# SCH_MCP_41x_453x.net
KiCad netlist of a schematic drawn in Altium Designer
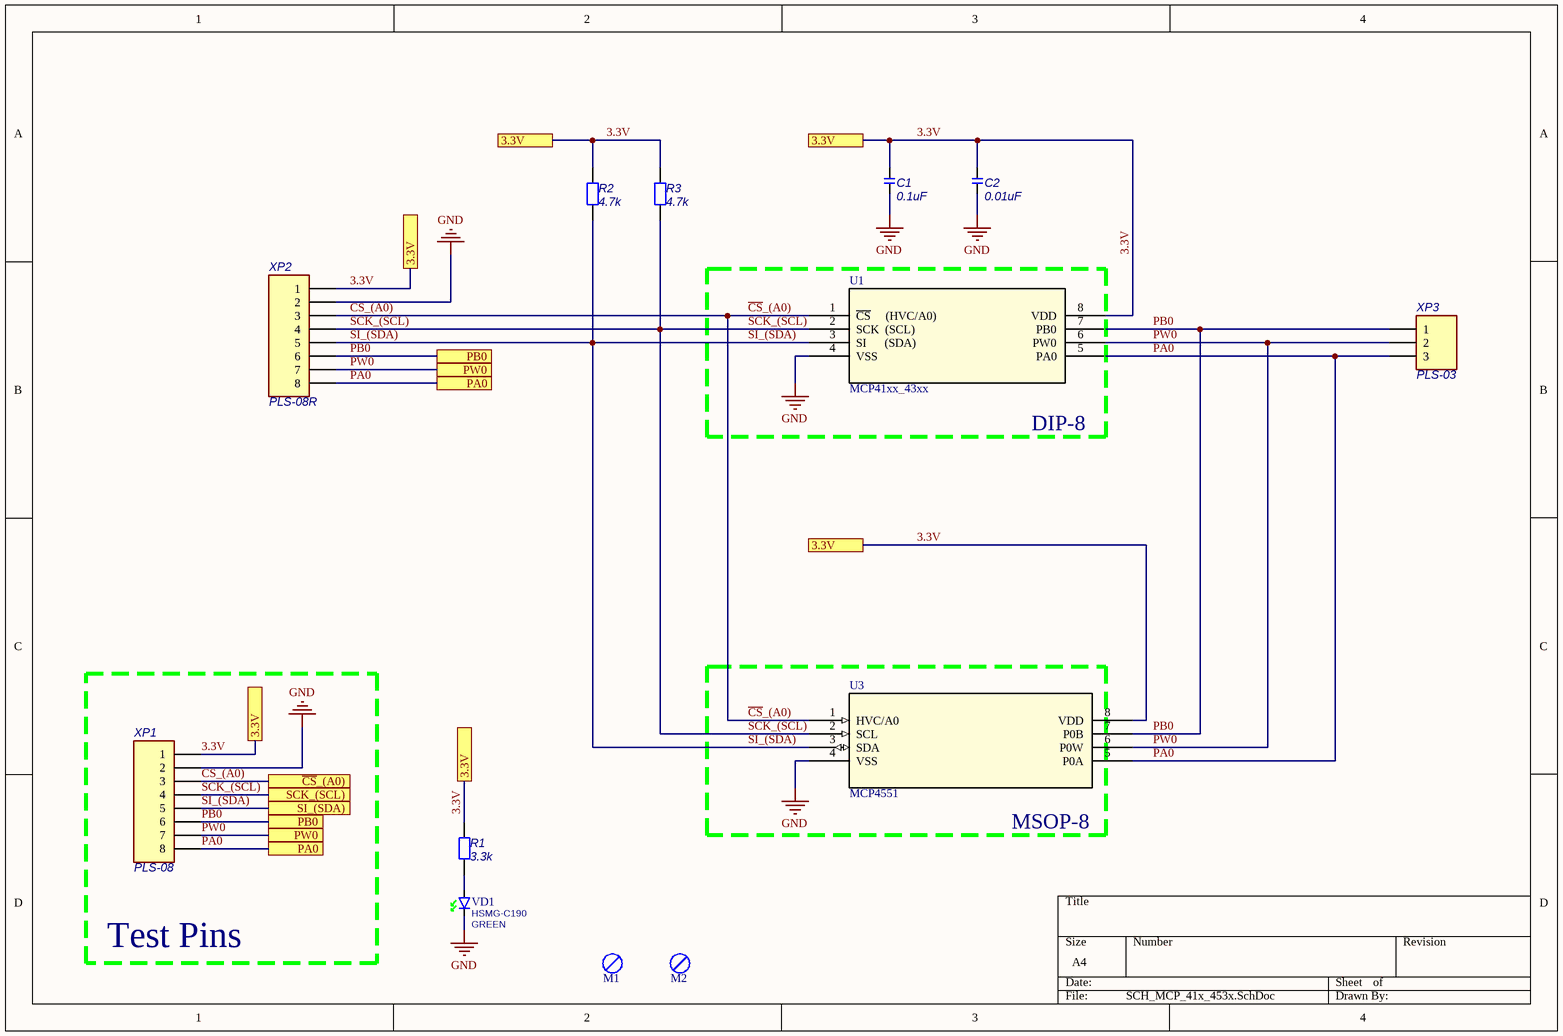
[diagram p0: SCH_MCP_41x_453x.SchDoc]

(export (version "E")
  (design (tool "Eeschema 10.0.6"))
  (components
    (comp (ref "C1")
      (value "0.1uF")
      (footprint "SMD0603-v3")
      (description "Конденсатор неполярный")
      (fields
        (field (name "PART NUMBER") "SMD0603-0.1uF-50V")
        (field (name "MANUFACTURER") "Rohm Semiconductor")
        (field (name "AUTHOR") "Sun")
      )
      (libsource (lib "MyDataBae") (part "Cap1"))
    )
    (comp (ref "C2")
      (value "0.01uF")
      (footprint "SMD0603-v3")
      (description "Конденсатор неполярный")
      (fields (field (name "PART NUMBER") "SMD0603-0.01uF-50V") (field (name "AUTHOR") "Sun"))
      (libsource (lib "MyDataBae") (part "Cap1"))
    )
    (comp (ref "M1")
      (value "Mehanical_Pin")
      (footprint "Mehanical_Pin")
      (fields (field (name "PART NUMBER") "Mehanical_PIN"))
      (libsource (lib "MyDataBae") (part "Mehanical_Pin"))
    )
    (comp (ref "M2")
      (value "Mehanical_Pin")
      (footprint "Mehanical_Pin")
      (fields (field (name "PART NUMBER") "Mehanical_PIN"))
      (libsource (lib "MyDataBae") (part "Mehanical_Pin"))
    )
    (comp (ref "R1")
      (value "3.3k")
      (footprint "SMD0603-v1")
      (description "Резистор постоянный")
      (fields
        (field (name "PART NUMBER") "SMD0603-3.3k-1%")
        (field (name "MANUFACTURER") "Rohm Semiconductor")
        (field (name "AUTHOR") "Sun")
      )
      (libsource (lib "MyDataBae") (part "Res1"))
    )
    (comp (ref "R2")
      (value "4.7k")
      (footprint "SMD0603-v1")
      (description "Резистор постоянный")
      (fields
        (field (name "PART NUMBER") "SMD0603-4.7k-1%")
        (field (name "MANUFACTURER") "Rohm Semiconductor")
        (field (name "AUTHOR") "Sun")
      )
      (libsource (lib "MyDataBae") (part "Res1"))
    )
    (comp (ref "R3")
      (value "4.7k")
      (footprint "SMD0603-v1")
      (description "Резистор постоянный")
      (fields
        (field (name "PART NUMBER") "SMD0603-4.7k-1%")
        (field (name "MANUFACTURER") "Rohm Semiconductor")
        (field (name "AUTHOR") "Sun")
      )
      (libsource (lib "MyDataBae") (part "Res1"))
    )
    (comp (ref "U1")
      (value "MCP41xx_43xx")
      (footprint "DIP-8_3D")
      (description "Digital Potentiometer with SPI or I2C Interface")
      (fields
        (field (name "MANUFACTURER_PART_NUMBER") "MCP41010T-E/SN")
        (field (name "MANUFACTURER") "Microchip")
        (field (name "COPYRIGHT") "Copyright (C) 2021 Ultra Librarian. All rights reserved.")
      )
      (libsource (lib "MyDataBae") (part "MCP41_43"))
    )
    (comp (ref "U3")
      (value "MCP4551")
      (footprint "SOP65P490X109-8N")
      (description "Digital Potentiometer with I2C Interface, 257 steps, Memory type: RAM")
      (fields
        (field (name "MANUFACTURER_PART_NUMBER") "MCP4531-103E/MS")
        (field (name "MANUFACTURER") "Microchip")
        (field (name "COPYRIGHT") "Copyright (C) 2021 Ultra Librarian. All rights reserved.")
      )
      (libsource (lib "MyDataBae") (part "MCP45xx"))
    )
    (comp (ref "VD1")
      (value "LED")
      (footprint "LEDC1608X80N_G")
      (description "Surface mount LED green 20mA")
      (fields
        (field (name "MANUFACTURER PART NO.") "HSMG-C190")
        (field (name "COLOR") "GREEN")
        (field (name "PART NUMBER") "LED-Avago-HSMG-C190_Green")
      )
      (libsource (lib "MyDataBae") (part "LED-Avago-HSMG-C190_Green"))
    )
    (comp (ref "XP1")
      (value "PLS-08")
      (footprint "PLS-08")
      (description "Однорядный прямой штыревой соединитель")
      (fields (field (name "MANUFACTURER") "BrownBear") (field (name "AUTHOR") "Gr."))
      (libsource (lib "MyDataBae") (part "Header-8"))
    )
    (comp (ref "XP2")
      (value "PLS-08R")
      (footprint "PLS-08R-LEFT")
      (description "Однорядный угловой штыревой соединитель")
      (fields (field (name "MANUFACTURER") "BrownBear") (field (name "AUTHOR") "Gr."))
      (libsource (lib "MyDataBae") (part "Header-8"))
    )
    (comp (ref "XP3")
      (value "PLS-03")
      (footprint "PLS-03")
      (description "Однорядный прямой штыревой соединитель")
      (fields (field (name "MANUFACTURER") "BrownBear") (field (name "AUTHOR") "Gr."))
      (libsource (lib "MyDataBae") (part "Header-3"))
    )
  )
  (nets
    (net (code "1") (name "/3.3V") (class "Default")
      (node (ref "C1") (pin "2") (pinfunction "2_2") (pintype "passive"))
      (node (ref "C2") (pin "2") (pinfunction "2_2") (pintype "passive"))
      (node (ref "R1") (pin "2") (pinfunction "2_2") (pintype "passive"))
      (node (ref "R2") (pin "2") (pinfunction "2_2") (pintype "passive"))
      (node (ref "R3") (pin "2") (pinfunction "2_2") (pintype "passive"))
      (node (ref "U1") (pin "8") (pinfunction "VDD_8") (pintype "passive"))
      (node (ref "U3") (pin "8") (pinfunction "VDD_8") (pintype "power_in"))
      (node (ref "XP1") (pin "1") (pinfunction "1_1") (pintype "passive"))
      (node (ref "XP2") (pin "1") (pinfunction "1_1") (pintype "passive"))
    )
    (net (code "2") (name "/PA0") (class "Default")
      (node (ref "U1") (pin "5") (pinfunction "PA0_5") (pintype "passive"))
      (node (ref "U3") (pin "5") (pinfunction "P0A_5") (pintype "passive"))
      (node (ref "XP1") (pin "8") (pinfunction "8_8") (pintype "passive"))
      (node (ref "XP2") (pin "8") (pinfunction "8_8") (pintype "passive"))
      (node (ref "XP3") (pin "3") (pinfunction "3_3") (pintype "passive"))
    )
    (net (code "3") (name "/PB0") (class "Default")
      (node (ref "U1") (pin "7") (pinfunction "PB0_7") (pintype "passive"))
      (node (ref "U3") (pin "7") (pinfunction "P0B_7") (pintype "passive"))
      (node (ref "XP1") (pin "6") (pinfunction "6_6") (pintype "passive"))
      (node (ref "XP2") (pin "6") (pinfunction "6_6") (pintype "passive"))
      (node (ref "XP3") (pin "1") (pinfunction "1_1") (pintype "passive"))
    )
    (net (code "4") (name "/PW0") (class "Default")
      (node (ref "U1") (pin "6") (pinfunction "PW0_6") (pintype "passive"))
      (node (ref "U3") (pin "6") (pinfunction "P0W_6") (pintype "passive"))
      (node (ref "XP1") (pin "7") (pinfunction "7_7") (pintype "passive"))
      (node (ref "XP2") (pin "7") (pinfunction "7_7") (pintype "passive"))
      (node (ref "XP3") (pin "2") (pinfunction "2_2") (pintype "passive"))
    )
    (net (code "5") (name "/SCK_(SCL)") (class "Default")
      (node (ref "R3") (pin "1") (pinfunction "1_1") (pintype "passive"))
      (node (ref "U1") (pin "2") (pinfunction "SCK__(SCL)_2") (pintype "passive"))
      (node (ref "U3") (pin "2") (pinfunction "SCL_2") (pintype "input"))
      (node (ref "XP1") (pin "4") (pinfunction "4_4") (pintype "passive"))
      (node (ref "XP2") (pin "4") (pinfunction "4_4") (pintype "passive"))
    )
    (net (code "6") (name "/SI_(SDA)") (class "Default")
      (node (ref "R2") (pin "1") (pinfunction "1_1") (pintype "passive"))
      (node (ref "U1") (pin "3") (pinfunction "SI______(SDA)_3") (pintype "passive"))
      (node (ref "U3") (pin "3") (pinfunction "SDA_3") (pintype "bidirectional"))
      (node (ref "XP1") (pin "5") (pinfunction "5_5") (pintype "passive"))
      (node (ref "XP2") (pin "5") (pinfunction "5_5") (pintype "passive"))
    )
    (net (code "7") (name "/~{CS}_(A0)") (class "Default")
      (node (ref "U1") (pin "1") (pinfunction "~{CS}_____(HVC/A0)_1") (pintype "passive"))
      (node (ref "U3") (pin "1") (pinfunction "HVC/A0_1") (pintype "input"))
      (node (ref "XP1") (pin "3") (pinfunction "3_3") (pintype "passive"))
      (node (ref "XP2") (pin "3") (pinfunction "3_3") (pintype "passive"))
    )
    (net (code "8") (name "GND") (class "Default")
      (node (ref "C1") (pin "1") (pinfunction "1_1") (pintype "passive"))
      (node (ref "C2") (pin "1") (pinfunction "1_1") (pintype "passive"))
      (node (ref "U1") (pin "4") (pinfunction "VSS_4") (pintype "passive"))
      (node (ref "U3") (pin "4") (pinfunction "VSS_4") (pintype "power_in"))
      (node (ref "VD1") (pin "1") (pinfunction "K_1") (pintype "passive"))
      (node (ref "XP1") (pin "2") (pinfunction "2_2") (pintype "passive"))
      (node (ref "XP2") (pin "2") (pinfunction "2_2") (pintype "passive"))
    )
    (net (code "9") (name "Net-(VD1-A)") (class "Default")
      (node (ref "R1") (pin "1") (pinfunction "1_1") (pintype "passive"))
      (node (ref "VD1") (pin "2") (pinfunction "A_2") (pintype "passive"))
    )
    (net (code "10") (name "unconnected-(M1-PadM)") (class "Default")
      (node (ref "M1") (pin "M") (pinfunction "M_M") (pintype "passive"))
    )
    (net (code "11") (name "unconnected-(M2-PadM)") (class "Default")
      (node (ref "M2") (pin "M") (pinfunction "M_M") (pintype "passive"))
    )
  )
)
